# mother2.net
KiCad netlist of a schematic drawn in EAGLE
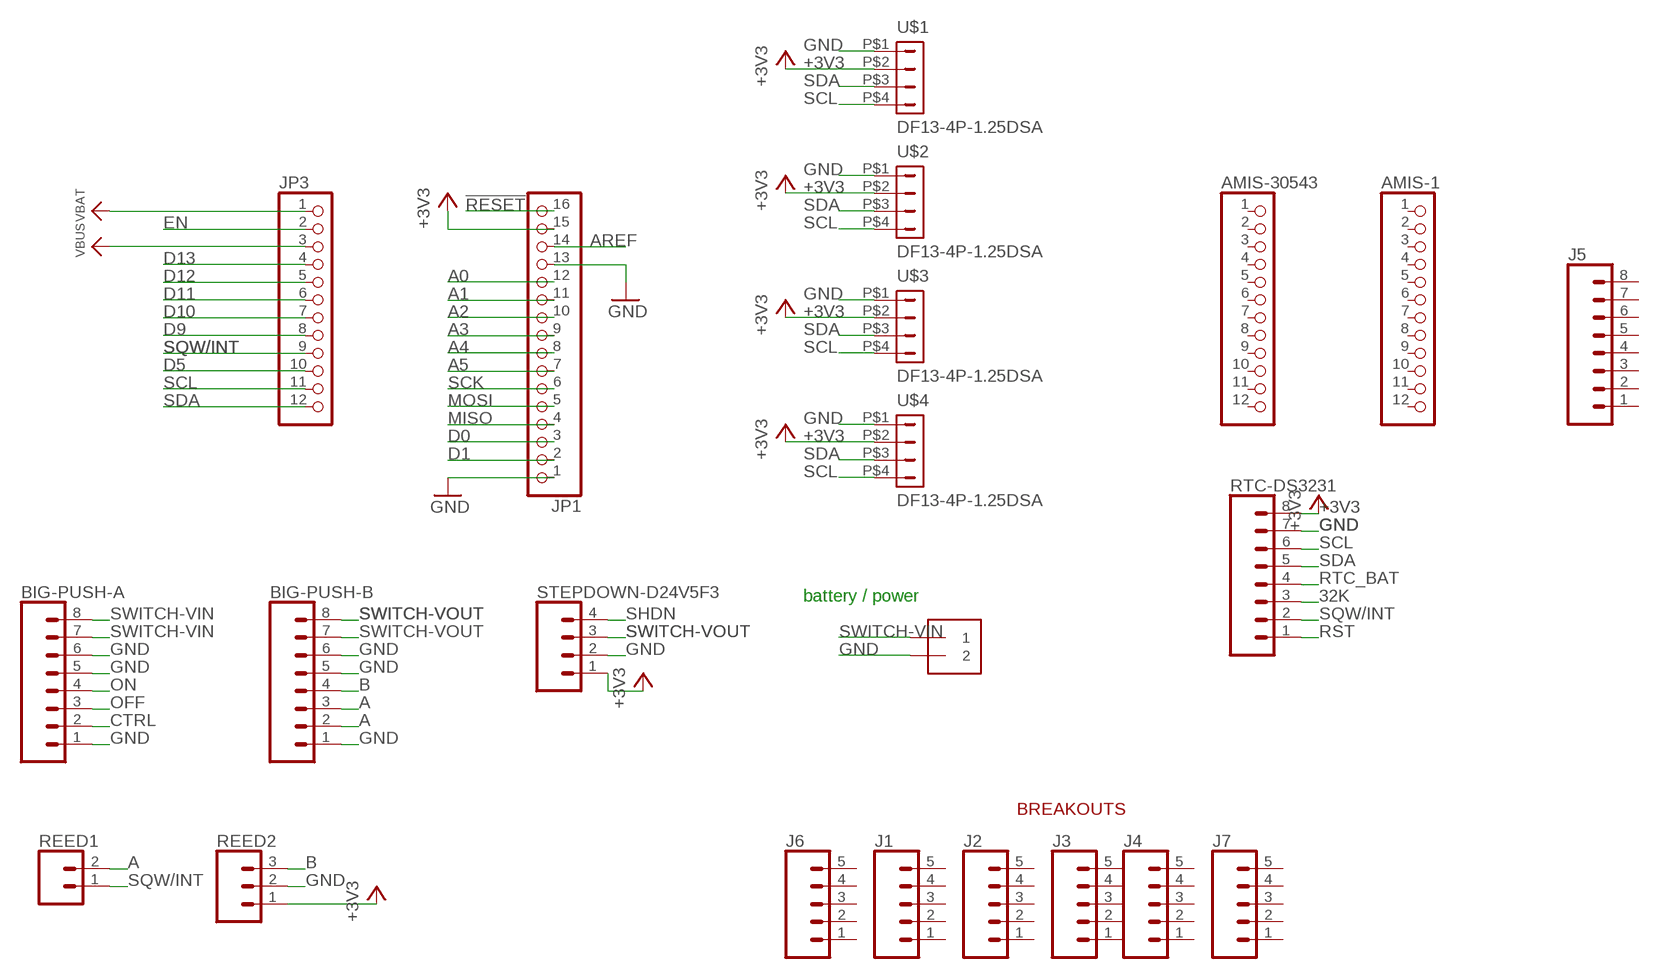
[diagram p0: schematic, sheet 1]

(export (version "E")
  (design (tool "Eeschema 10.0.6"))
  (components
    (comp (ref "AMIS-1")
      (value "PINHD-1X12-CB")
      (footprint "eagle-import:1X12-CB")
      (libsource (lib "eagle-import") (part "PINHD-1X12-CB"))
    )
    (comp (ref "AMIS-30543")
      (value "PINHD-1X12-CB")
      (footprint "eagle-import:1X12-CB")
      (libsource (lib "eagle-import") (part "PINHD-1X12-CB"))
    )
    (comp (ref "BAT")
      (value "1X2-3.5MM")
      (footprint "eagle-import:1X2-3.5MM")
      (libsource (lib "eagle-import") (part "1X2-3.5MM"))
    )
    (comp (ref "BIG-PUSH-A")
      (value "CONN_08\"")
      (footprint "eagle-import:1X08")
      (libsource (lib "eagle-import") (part "CONN_08{dblquote}"))
    )
    (comp (ref "BIG-PUSH-B")
      (value "CONN_08\"")
      (footprint "eagle-import:1X08")
      (libsource (lib "eagle-import") (part "CONN_08{dblquote}"))
    )
    (comp (ref "J1")
      (value "CONN_05")
      (footprint "eagle-import:1X05")
      (libsource (lib "eagle-import") (part "CONN_05"))
    )
    (comp (ref "J2")
      (value "CONN_05")
      (footprint "eagle-import:1X05")
      (libsource (lib "eagle-import") (part "CONN_05"))
    )
    (comp (ref "J3")
      (value "CONN_05")
      (footprint "eagle-import:1X05")
      (libsource (lib "eagle-import") (part "CONN_05"))
    )
    (comp (ref "J4")
      (value "CONN_05")
      (footprint "eagle-import:1X05")
      (libsource (lib "eagle-import") (part "CONN_05"))
    )
    (comp (ref "J5")
      (value "CONN_08\"")
      (footprint "eagle-import:1X08")
      (libsource (lib "eagle-import") (part "CONN_08{dblquote}"))
    )
    (comp (ref "J6")
      (value "CONN_05")
      (footprint "eagle-import:1X05")
      (libsource (lib "eagle-import") (part "CONN_05"))
    )
    (comp (ref "J7")
      (value "CONN_05")
      (footprint "eagle-import:1X05")
      (libsource (lib "eagle-import") (part "CONN_05"))
    )
    (comp (ref "JP1")
      (value "HEADER-1X16ROUND")
      (footprint "eagle-import:1X16_ROUND")
      (libsource (lib "eagle-import") (part "HEADER-1X16ROUND"))
    )
    (comp (ref "JP3")
      (value "HEADER-1X12")
      (footprint "eagle-import:1X12_ROUND")
      (libsource (lib "eagle-import") (part "HEADER-1X12"))
    )
    (comp (ref "REED1")
      (value "CONN_02")
      (footprint "eagle-import:1X02")
      (libsource (lib "eagle-import") (part "CONN_02"))
    )
    (comp (ref "REED2")
      (value "CONN_03")
      (footprint "eagle-import:1X03")
      (libsource (lib "eagle-import") (part "CONN_03"))
    )
    (comp (ref "RTC-DS3231")
      (value "CONN_08\"")
      (footprint "eagle-import:1X08")
      (libsource (lib "eagle-import") (part "CONN_08{dblquote}"))
    )
    (comp (ref "STEPDOWN-D24V5F3")
      (value "CONN_04")
      (footprint "eagle-import:1X04")
      (libsource (lib "eagle-import") (part "CONN_04"))
    )
    (comp (ref "U$1")
      (value "DF13-4P-1.25DSA")
      (footprint "eagle-import:DF13-4P-1.25DSA")
      (libsource (lib "eagle-import") (part "DF13-4P-1.25DSA"))
    )
    (comp (ref "U$2")
      (value "DF13-4P-1.25DSA")
      (footprint "eagle-import:DF13-4P-1.25DSA")
      (libsource (lib "eagle-import") (part "DF13-4P-1.25DSA"))
    )
    (comp (ref "U$3")
      (value "DF13-4P-1.25DSA")
      (footprint "eagle-import:DF13-4P-1.25DSA")
      (libsource (lib "eagle-import") (part "DF13-4P-1.25DSA"))
    )
    (comp (ref "U$4")
      (value "DF13-4P-1.25DSA")
      (footprint "eagle-import:DF13-4P-1.25DSA")
      (libsource (lib "eagle-import") (part "DF13-4P-1.25DSA"))
    )
  )
  (nets
    (net (code "1") (name "+3V3") (class "Default")
      (node (ref "JP1") (pin "15") (pinfunction "15_15") (pintype "passive"))
      (node (ref "REED2") (pin "1") (pinfunction "1_1") (pintype "passive"))
      (node (ref "RTC-DS3231") (pin "8") (pinfunction "8_8") (pintype "passive"))
      (node (ref "STEPDOWN-D24V5F3") (pin "1") (pinfunction "1_1") (pintype "passive"))
      (node (ref "U$1") (pin "P$2") (pinfunction "2_P$2") (pintype "passive"))
      (node (ref "U$2") (pin "P$2") (pinfunction "2_P$2") (pintype "passive"))
      (node (ref "U$3") (pin "P$2") (pinfunction "2_P$2") (pintype "passive"))
      (node (ref "U$4") (pin "P$2") (pinfunction "2_P$2") (pintype "passive"))
    )
    (net (code "2") (name "/32K") (class "Default")
      (node (ref "RTC-DS3231") (pin "3") (pinfunction "3_3") (pintype "passive"))
    )
    (net (code "3") (name "/A") (class "Default")
      (node (ref "BIG-PUSH-B") (pin "2") (pinfunction "2_2") (pintype "passive"))
      (node (ref "BIG-PUSH-B") (pin "3") (pinfunction "3_3") (pintype "passive"))
      (node (ref "REED1") (pin "2") (pinfunction "2_2") (pintype "passive"))
    )
    (net (code "4") (name "/A0") (class "Default")
      (node (ref "JP1") (pin "12") (pinfunction "12_12") (pintype "passive"))
    )
    (net (code "5") (name "/A1") (class "Default")
      (node (ref "JP1") (pin "11") (pinfunction "11_11") (pintype "passive"))
    )
    (net (code "6") (name "/A2") (class "Default")
      (node (ref "JP1") (pin "10") (pinfunction "10_10") (pintype "passive"))
    )
    (net (code "7") (name "/A3") (class "Default")
      (node (ref "JP1") (pin "9") (pinfunction "9_9") (pintype "passive"))
    )
    (net (code "8") (name "/A4") (class "Default")
      (node (ref "JP1") (pin "8") (pinfunction "8_8") (pintype "passive"))
    )
    (net (code "9") (name "/A5") (class "Default")
      (node (ref "JP1") (pin "7") (pinfunction "7_7") (pintype "passive"))
    )
    (net (code "10") (name "/AREF") (class "Default")
      (node (ref "JP1") (pin "14") (pinfunction "14_14") (pintype "passive"))
    )
    (net (code "11") (name "/B") (class "Default")
      (node (ref "BIG-PUSH-B") (pin "4") (pinfunction "4_4") (pintype "passive"))
      (node (ref "REED2") (pin "3") (pinfunction "3_3") (pintype "passive"))
    )
    (net (code "12") (name "/CTRL") (class "Default")
      (node (ref "BIG-PUSH-A") (pin "2") (pinfunction "2_2") (pintype "passive"))
    )
    (net (code "13") (name "/D0") (class "Default")
      (node (ref "JP1") (pin "3") (pinfunction "3_3") (pintype "passive"))
    )
    (net (code "14") (name "/D1") (class "Default")
      (node (ref "JP1") (pin "2") (pinfunction "2_2") (pintype "passive"))
    )
    (net (code "15") (name "/D5") (class "Default")
      (node (ref "JP3") (pin "10") (pinfunction "10_10") (pintype "passive"))
    )
    (net (code "16") (name "/D9") (class "Default")
      (node (ref "JP3") (pin "8") (pinfunction "8_8") (pintype "passive"))
    )
    (net (code "17") (name "/D10") (class "Default")
      (node (ref "JP3") (pin "7") (pinfunction "7_7") (pintype "passive"))
    )
    (net (code "18") (name "/D11") (class "Default")
      (node (ref "JP3") (pin "6") (pinfunction "6_6") (pintype "passive"))
    )
    (net (code "19") (name "/D12") (class "Default")
      (node (ref "JP3") (pin "5") (pinfunction "5_5") (pintype "passive"))
    )
    (net (code "20") (name "/D13") (class "Default")
      (node (ref "JP3") (pin "4") (pinfunction "4_4") (pintype "passive"))
    )
    (net (code "21") (name "/EN") (class "Default")
      (node (ref "JP3") (pin "2") (pinfunction "2_2") (pintype "passive"))
    )
    (net (code "22") (name "/MISO") (class "Default")
      (node (ref "JP1") (pin "4") (pinfunction "4_4") (pintype "passive"))
    )
    (net (code "23") (name "/MOSI") (class "Default")
      (node (ref "JP1") (pin "5") (pinfunction "5_5") (pintype "passive"))
    )
    (net (code "24") (name "/OFF") (class "Default")
      (node (ref "BIG-PUSH-A") (pin "3") (pinfunction "3_3") (pintype "passive"))
    )
    (net (code "25") (name "/ON") (class "Default")
      (node (ref "BIG-PUSH-A") (pin "4") (pinfunction "4_4") (pintype "passive"))
    )
    (net (code "26") (name "/RST") (class "Default")
      (node (ref "RTC-DS3231") (pin "1") (pinfunction "1_1") (pintype "passive"))
    )
    (net (code "27") (name "/RTC_BAT") (class "Default")
      (node (ref "RTC-DS3231") (pin "4") (pinfunction "4_4") (pintype "passive"))
    )
    (net (code "28") (name "/SCK") (class "Default")
      (node (ref "JP1") (pin "6") (pinfunction "6_6") (pintype "passive"))
    )
    (net (code "29") (name "/SCL") (class "Default")
      (node (ref "JP3") (pin "11") (pinfunction "11_11") (pintype "passive"))
      (node (ref "RTC-DS3231") (pin "6") (pinfunction "6_6") (pintype "passive"))
      (node (ref "U$1") (pin "P$4") (pinfunction "4_P$4") (pintype "passive"))
      (node (ref "U$2") (pin "P$4") (pinfunction "4_P$4") (pintype "passive"))
      (node (ref "U$3") (pin "P$4") (pinfunction "4_P$4") (pintype "passive"))
      (node (ref "U$4") (pin "P$4") (pinfunction "4_P$4") (pintype "passive"))
    )
    (net (code "30") (name "/SDA") (class "Default")
      (node (ref "JP3") (pin "12") (pinfunction "12_12") (pintype "passive"))
      (node (ref "RTC-DS3231") (pin "5") (pinfunction "5_5") (pintype "passive"))
      (node (ref "U$1") (pin "P$3") (pinfunction "3_P$3") (pintype "passive"))
      (node (ref "U$2") (pin "P$3") (pinfunction "3_P$3") (pintype "passive"))
      (node (ref "U$3") (pin "P$3") (pinfunction "3_P$3") (pintype "passive"))
      (node (ref "U$4") (pin "P$3") (pinfunction "3_P$3") (pintype "passive"))
    )
    (net (code "31") (name "/SHDN") (class "Default")
      (node (ref "STEPDOWN-D24V5F3") (pin "4") (pinfunction "4_4") (pintype "passive"))
    )
    (net (code "32") (name "/SQW{slash}INT") (class "Default")
      (node (ref "JP3") (pin "9") (pinfunction "9_9") (pintype "passive"))
      (node (ref "REED1") (pin "1") (pinfunction "1_1") (pintype "passive"))
      (node (ref "RTC-DS3231") (pin "2") (pinfunction "2_2") (pintype "passive"))
    )
    (net (code "33") (name "/SWITCH-VIN") (class "Default")
      (node (ref "BAT") (pin "1") (pinfunction "1_1") (pintype "passive"))
      (node (ref "BIG-PUSH-A") (pin "7") (pinfunction "7_7") (pintype "passive"))
      (node (ref "BIG-PUSH-A") (pin "8") (pinfunction "8_8") (pintype "passive"))
    )
    (net (code "34") (name "/SWITCH-VOUT") (class "Default")
      (node (ref "BIG-PUSH-B") (pin "7") (pinfunction "7_7") (pintype "passive"))
      (node (ref "BIG-PUSH-B") (pin "8") (pinfunction "8_8") (pintype "passive"))
      (node (ref "STEPDOWN-D24V5F3") (pin "3") (pinfunction "3_3") (pintype "passive"))
    )
    (net (code "35") (name "/~{RESET}") (class "Default")
      (node (ref "JP1") (pin "16") (pinfunction "16_16") (pintype "passive"))
    )
    (net (code "36") (name "GND") (class "Default")
      (node (ref "BAT") (pin "2") (pinfunction "2_2") (pintype "passive"))
      (node (ref "BIG-PUSH-A") (pin "1") (pinfunction "1_1") (pintype "passive"))
      (node (ref "BIG-PUSH-A") (pin "5") (pinfunction "5_5") (pintype "passive"))
      (node (ref "BIG-PUSH-A") (pin "6") (pinfunction "6_6") (pintype "passive"))
      (node (ref "BIG-PUSH-B") (pin "1") (pinfunction "1_1") (pintype "passive"))
      (node (ref "BIG-PUSH-B") (pin "5") (pinfunction "5_5") (pintype "passive"))
      (node (ref "BIG-PUSH-B") (pin "6") (pinfunction "6_6") (pintype "passive"))
      (node (ref "JP1") (pin "1") (pinfunction "1_1") (pintype "passive"))
      (node (ref "JP1") (pin "13") (pinfunction "13_13") (pintype "passive"))
      (node (ref "REED2") (pin "2") (pinfunction "2_2") (pintype "passive"))
      (node (ref "RTC-DS3231") (pin "7") (pinfunction "7_7") (pintype "passive"))
      (node (ref "STEPDOWN-D24V5F3") (pin "2") (pinfunction "2_2") (pintype "passive"))
      (node (ref "U$1") (pin "P$1") (pinfunction "1_P$1") (pintype "passive"))
      (node (ref "U$2") (pin "P$1") (pinfunction "1_P$1") (pintype "passive"))
      (node (ref "U$3") (pin "P$1") (pinfunction "1_P$1") (pintype "passive"))
      (node (ref "U$4") (pin "P$1") (pinfunction "1_P$1") (pintype "passive"))
    )
    (net (code "37") (name "VBAT") (class "Default")
      (node (ref "JP3") (pin "1") (pinfunction "1_1") (pintype "passive"))
    )
    (net (code "38") (name "VBUS") (class "Default")
      (node (ref "JP3") (pin "3") (pinfunction "3_3") (pintype "passive"))
    )
    (net (code "39") (name "unconnected-(AMIS-1-Pad1)") (class "Default")
      (node (ref "AMIS-1") (pin "1") (pinfunction "1_1") (pintype "passive"))
    )
    (net (code "40") (name "unconnected-(AMIS-1-Pad2)") (class "Default")
      (node (ref "AMIS-1") (pin "2") (pinfunction "2_2") (pintype "passive"))
    )
    (net (code "41") (name "unconnected-(AMIS-1-Pad3)") (class "Default")
      (node (ref "AMIS-1") (pin "3") (pinfunction "3_3") (pintype "passive"))
    )
    (net (code "42") (name "unconnected-(AMIS-1-Pad4)") (class "Default")
      (node (ref "AMIS-1") (pin "4") (pinfunction "4_4") (pintype "passive"))
    )
    (net (code "43") (name "unconnected-(AMIS-1-Pad5)") (class "Default")
      (node (ref "AMIS-1") (pin "5") (pinfunction "5_5") (pintype "passive"))
    )
    (net (code "44") (name "unconnected-(AMIS-1-Pad6)") (class "Default")
      (node (ref "AMIS-1") (pin "6") (pinfunction "6_6") (pintype "passive"))
    )
    (net (code "45") (name "unconnected-(AMIS-1-Pad7)") (class "Default")
      (node (ref "AMIS-1") (pin "7") (pinfunction "7_7") (pintype "passive"))
    )
    (net (code "46") (name "unconnected-(AMIS-1-Pad8)") (class "Default")
      (node (ref "AMIS-1") (pin "8") (pinfunction "8_8") (pintype "passive"))
    )
    (net (code "47") (name "unconnected-(AMIS-1-Pad9)") (class "Default")
      (node (ref "AMIS-1") (pin "9") (pinfunction "9_9") (pintype "passive"))
    )
    (net (code "48") (name "unconnected-(AMIS-1-Pad10)") (class "Default")
      (node (ref "AMIS-1") (pin "10") (pinfunction "10_10") (pintype "passive"))
    )
    (net (code "49") (name "unconnected-(AMIS-1-Pad11)") (class "Default")
      (node (ref "AMIS-1") (pin "11") (pinfunction "11_11") (pintype "passive"))
    )
    (net (code "50") (name "unconnected-(AMIS-1-Pad12)") (class "Default")
      (node (ref "AMIS-1") (pin "12") (pinfunction "12_12") (pintype "passive"))
    )
    (net (code "51") (name "unconnected-(AMIS-30543-Pad1)") (class "Default")
      (node (ref "AMIS-30543") (pin "1") (pinfunction "1_1") (pintype "passive"))
    )
    (net (code "52") (name "unconnected-(AMIS-30543-Pad2)") (class "Default")
      (node (ref "AMIS-30543") (pin "2") (pinfunction "2_2") (pintype "passive"))
    )
    (net (code "53") (name "unconnected-(AMIS-30543-Pad3)") (class "Default")
      (node (ref "AMIS-30543") (pin "3") (pinfunction "3_3") (pintype "passive"))
    )
    (net (code "54") (name "unconnected-(AMIS-30543-Pad4)") (class "Default")
      (node (ref "AMIS-30543") (pin "4") (pinfunction "4_4") (pintype "passive"))
    )
    (net (code "55") (name "unconnected-(AMIS-30543-Pad5)") (class "Default")
      (node (ref "AMIS-30543") (pin "5") (pinfunction "5_5") (pintype "passive"))
    )
    (net (code "56") (name "unconnected-(AMIS-30543-Pad6)") (class "Default")
      (node (ref "AMIS-30543") (pin "6") (pinfunction "6_6") (pintype "passive"))
    )
    (net (code "57") (name "unconnected-(AMIS-30543-Pad7)") (class "Default")
      (node (ref "AMIS-30543") (pin "7") (pinfunction "7_7") (pintype "passive"))
    )
    (net (code "58") (name "unconnected-(AMIS-30543-Pad8)") (class "Default")
      (node (ref "AMIS-30543") (pin "8") (pinfunction "8_8") (pintype "passive"))
    )
    (net (code "59") (name "unconnected-(AMIS-30543-Pad9)") (class "Default")
      (node (ref "AMIS-30543") (pin "9") (pinfunction "9_9") (pintype "passive"))
    )
    (net (code "60") (name "unconnected-(AMIS-30543-Pad10)") (class "Default")
      (node (ref "AMIS-30543") (pin "10") (pinfunction "10_10") (pintype "passive"))
    )
    (net (code "61") (name "unconnected-(AMIS-30543-Pad11)") (class "Default")
      (node (ref "AMIS-30543") (pin "11") (pinfunction "11_11") (pintype "passive"))
    )
    (net (code "62") (name "unconnected-(AMIS-30543-Pad12)") (class "Default")
      (node (ref "AMIS-30543") (pin "12") (pinfunction "12_12") (pintype "passive"))
    )
    (net (code "63") (name "unconnected-(J1-Pad1)") (class "Default")
      (node (ref "J1") (pin "1") (pinfunction "1_1") (pintype "passive"))
    )
    (net (code "64") (name "unconnected-(J1-Pad2)") (class "Default")
      (node (ref "J1") (pin "2") (pinfunction "2_2") (pintype "passive"))
    )
    (net (code "65") (name "unconnected-(J1-Pad3)") (class "Default")
      (node (ref "J1") (pin "3") (pinfunction "3_3") (pintype "passive"))
    )
    (net (code "66") (name "unconnected-(J1-Pad4)") (class "Default")
      (node (ref "J1") (pin "4") (pinfunction "4_4") (pintype "passive"))
    )
    (net (code "67") (name "unconnected-(J1-Pad5)") (class "Default")
      (node (ref "J1") (pin "5") (pinfunction "5_5") (pintype "passive"))
    )
    (net (code "68") (name "unconnected-(J2-Pad1)") (class "Default")
      (node (ref "J2") (pin "1") (pinfunction "1_1") (pintype "passive"))
    )
    (net (code "69") (name "unconnected-(J2-Pad2)") (class "Default")
      (node (ref "J2") (pin "2") (pinfunction "2_2") (pintype "passive"))
    )
    (net (code "70") (name "unconnected-(J2-Pad3)") (class "Default")
      (node (ref "J2") (pin "3") (pinfunction "3_3") (pintype "passive"))
    )
    (net (code "71") (name "unconnected-(J2-Pad4)") (class "Default")
      (node (ref "J2") (pin "4") (pinfunction "4_4") (pintype "passive"))
    )
    (net (code "72") (name "unconnected-(J2-Pad5)") (class "Default")
      (node (ref "J2") (pin "5") (pinfunction "5_5") (pintype "passive"))
    )
    (net (code "73") (name "unconnected-(J3-Pad1)") (class "Default")
      (node (ref "J3") (pin "1") (pinfunction "1_1") (pintype "passive"))
    )
    (net (code "74") (name "unconnected-(J3-Pad2)") (class "Default")
      (node (ref "J3") (pin "2") (pinfunction "2_2") (pintype "passive"))
    )
    (net (code "75") (name "unconnected-(J3-Pad3)") (class "Default")
      (node (ref "J3") (pin "3") (pinfunction "3_3") (pintype "passive"))
    )
    (net (code "76") (name "unconnected-(J3-Pad4)") (class "Default")
      (node (ref "J3") (pin "4") (pinfunction "4_4") (pintype "passive"))
    )
    (net (code "77") (name "unconnected-(J3-Pad5)") (class "Default")
      (node (ref "J3") (pin "5") (pinfunction "5_5") (pintype "passive"))
    )
    (net (code "78") (name "unconnected-(J4-Pad1)") (class "Default")
      (node (ref "J4") (pin "1") (pinfunction "1_1") (pintype "passive"))
    )
    (net (code "79") (name "unconnected-(J4-Pad2)") (class "Default")
      (node (ref "J4") (pin "2") (pinfunction "2_2") (pintype "passive"))
    )
    (net (code "80") (name "unconnected-(J4-Pad3)") (class "Default")
      (node (ref "J4") (pin "3") (pinfunction "3_3") (pintype "passive"))
    )
    (net (code "81") (name "unconnected-(J4-Pad4)") (class "Default")
      (node (ref "J4") (pin "4") (pinfunction "4_4") (pintype "passive"))
    )
    (net (code "82") (name "unconnected-(J4-Pad5)") (class "Default")
      (node (ref "J4") (pin "5") (pinfunction "5_5") (pintype "passive"))
    )
    (net (code "83") (name "unconnected-(J5-Pad1)") (class "Default")
      (node (ref "J5") (pin "1") (pinfunction "1_1") (pintype "passive"))
    )
    (net (code "84") (name "unconnected-(J5-Pad2)") (class "Default")
      (node (ref "J5") (pin "2") (pinfunction "2_2") (pintype "passive"))
    )
    (net (code "85") (name "unconnected-(J5-Pad3)") (class "Default")
      (node (ref "J5") (pin "3") (pinfunction "3_3") (pintype "passive"))
    )
    (net (code "86") (name "unconnected-(J5-Pad4)") (class "Default")
      (node (ref "J5") (pin "4") (pinfunction "4_4") (pintype "passive"))
    )
    (net (code "87") (name "unconnected-(J5-Pad5)") (class "Default")
      (node (ref "J5") (pin "5") (pinfunction "5_5") (pintype "passive"))
    )
    (net (code "88") (name "unconnected-(J5-Pad6)") (class "Default")
      (node (ref "J5") (pin "6") (pinfunction "6_6") (pintype "passive"))
    )
    (net (code "89") (name "unconnected-(J5-Pad7)") (class "Default")
      (node (ref "J5") (pin "7") (pinfunction "7_7") (pintype "passive"))
    )
    (net (code "90") (name "unconnected-(J5-Pad8)") (class "Default")
      (node (ref "J5") (pin "8") (pinfunction "8_8") (pintype "passive"))
    )
    (net (code "91") (name "unconnected-(J6-Pad1)") (class "Default")
      (node (ref "J6") (pin "1") (pinfunction "1_1") (pintype "passive"))
    )
    (net (code "92") (name "unconnected-(J6-Pad2)") (class "Default")
      (node (ref "J6") (pin "2") (pinfunction "2_2") (pintype "passive"))
    )
    (net (code "93") (name "unconnected-(J6-Pad3)") (class "Default")
      (node (ref "J6") (pin "3") (pinfunction "3_3") (pintype "passive"))
    )
    (net (code "94") (name "unconnected-(J6-Pad4)") (class "Default")
      (node (ref "J6") (pin "4") (pinfunction "4_4") (pintype "passive"))
    )
    (net (code "95") (name "unconnected-(J6-Pad5)") (class "Default")
      (node (ref "J6") (pin "5") (pinfunction "5_5") (pintype "passive"))
    )
    (net (code "96") (name "unconnected-(J7-Pad1)") (class "Default")
      (node (ref "J7") (pin "1") (pinfunction "1_1") (pintype "passive"))
    )
    (net (code "97") (name "unconnected-(J7-Pad2)") (class "Default")
      (node (ref "J7") (pin "2") (pinfunction "2_2") (pintype "passive"))
    )
    (net (code "98") (name "unconnected-(J7-Pad3)") (class "Default")
      (node (ref "J7") (pin "3") (pinfunction "3_3") (pintype "passive"))
    )
    (net (code "99") (name "unconnected-(J7-Pad4)") (class "Default")
      (node (ref "J7") (pin "4") (pinfunction "4_4") (pintype "passive"))
    )
    (net (code "100") (name "unconnected-(J7-Pad5)") (class "Default")
      (node (ref "J7") (pin "5") (pinfunction "5_5") (pintype "passive"))
    )
  )
)
